# LightUpATtiny13.net
KiCad netlist of a schematic drawn in EAGLE
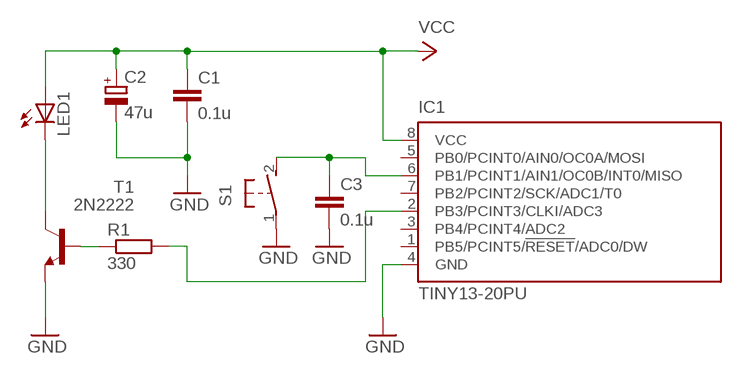
[diagram p0: schematic, sheet 1]

(export (version "E")
  (design (tool "Eeschema 10.0.6"))
  (components
    (comp (ref "C1")
      (value "0.1u")
      (footprint "eagle-import:C025-025X050")
      (libsource (lib "eagle-import") (part "C-EU025-025X050"))
    )
    (comp (ref "C2")
      (value "47u")
      (footprint "eagle-import:E2-5")
      (libsource (lib "eagle-import") (part "CPOL-EUE2-5"))
    )
    (comp (ref "C3")
      (value "0.1u")
      (footprint "eagle-import:C025-025X050")
      (libsource (lib "eagle-import") (part "C-EU025-025X050"))
    )
    (comp (ref "IC1")
      (value "TINY13-20PU")
      (footprint "eagle-import:DIL08")
      (fields (field (name "MPN") "ATTINY13-20PU"))
      (libsource (lib "eagle-import") (part "TINY13PU-20"))
    )
    (comp (ref "LED1")
      (value "LEDSQR2X5")
      (footprint "eagle-import:LED2X5")
      (libsource (lib "eagle-import") (part "LEDSQR2X5"))
    )
    (comp (ref "R1")
      (value "330")
      (footprint "eagle-import:0411_12")
      (libsource (lib "eagle-import") (part "R-EU_0411/12"))
    )
    (comp (ref "S1")
      (value "31-XX")
      (footprint "eagle-import:B3F-31XX")
      (fields (field (name "MPN") "B3F-3100"))
      (libsource (lib "eagle-import") (part "31-XX"))
    )
    (comp (ref "T1")
      (value "2N2222")
      (footprint "eagle-import:TO18")
      (libsource (lib "eagle-import") (part "2N2222"))
    )
  )
  (nets
    (net (code "1") (name "GND") (class "Default")
      (node (ref "C1") (pin "2") (pinfunction "2_2") (pintype "passive"))
      (node (ref "C2") (pin "-") (pinfunction "-_-") (pintype "passive"))
      (node (ref "C3") (pin "2") (pinfunction "2_2") (pintype "passive"))
      (node (ref "IC1") (pin "4") (pinfunction "GND_4") (pintype "power_in"))
      (node (ref "S1") (pin "1") (pinfunction "P_1") (pintype "passive"))
      (node (ref "T1") (pin "1") (pinfunction "E_1") (pintype "passive"))
    )
    (net (code "2") (name "Net-(IC1-PB1{slash}PCINT1{slash}AIN1{slash}OC0B{slash}INT0{slash}MISO)") (class "Default")
      (node (ref "C3") (pin "1") (pinfunction "1_1") (pintype "passive"))
      (node (ref "IC1") (pin "6") (pinfunction "PB1/PCINT1/AIN1/OC0B/INT0/MISO_6") (pintype "bidirectional"))
      (node (ref "S1") (pin "2") (pinfunction "S_2") (pintype "passive"))
    )
    (net (code "3") (name "Net-(IC1-PB3{slash}PCINT3{slash}CLKI{slash}ADC3)") (class "Default")
      (node (ref "IC1") (pin "2") (pinfunction "PB3/PCINT3/CLKI/ADC3_2") (pintype "bidirectional"))
      (node (ref "R1") (pin "2") (pinfunction "2_2") (pintype "passive"))
    )
    (net (code "4") (name "Net-(LED1-C)") (class "Default")
      (node (ref "LED1") (pin "K") (pinfunction "C_K") (pintype "passive"))
      (node (ref "T1") (pin "3") (pinfunction "C_3") (pintype "passive"))
    )
    (net (code "5") (name "Net-(T1-B)") (class "Default")
      (node (ref "R1") (pin "1") (pinfunction "1_1") (pintype "passive"))
      (node (ref "T1") (pin "2") (pinfunction "B_2") (pintype "passive"))
    )
    (net (code "6") (name "VCC") (class "Default")
      (node (ref "C1") (pin "1") (pinfunction "1_1") (pintype "passive"))
      (node (ref "C2") (pin "+") (pinfunction "+_+") (pintype "passive"))
      (node (ref "IC1") (pin "8") (pinfunction "VCC_8") (pintype "power_in"))
      (node (ref "LED1") (pin "A") (pinfunction "A_A") (pintype "passive"))
    )
    (net (code "7") (name "unconnected-(IC1-PB0{slash}PCINT0{slash}AIN0{slash}OC0A{slash}MOSI-Pad5)") (class "Default")
      (node (ref "IC1") (pin "5") (pinfunction "PB0/PCINT0/AIN0/OC0A/MOSI_5") (pintype "bidirectional"))
    )
    (net (code "8") (name "unconnected-(IC1-PB2{slash}PCINT2{slash}SCK{slash}ADC1{slash}T0-Pad7)") (class "Default")
      (node (ref "IC1") (pin "7") (pinfunction "PB2/PCINT2/SCK/ADC1/T0_7") (pintype "bidirectional"))
    )
    (net (code "9") (name "unconnected-(IC1-PB4{slash}PCINT4{slash}ADC2-Pad3)") (class "Default")
      (node (ref "IC1") (pin "3") (pinfunction "PB4/PCINT4/ADC2_3") (pintype "bidirectional"))
    )
    (net (code "10") (name "unconnected-(IC1-PB5{slash}PCINT5{slash}~{RESET}{slash}ADC0{slash}DW-Pad1)") (class "Default")
      (node (ref "IC1") (pin "1") (pinfunction "PB5/PCINT5/~{RESET}/ADC0/DW_1") (pintype "bidirectional"))
    )
  )
)
